# Optic.net
KiCad netlist of a schematic drawn in Altium Designer
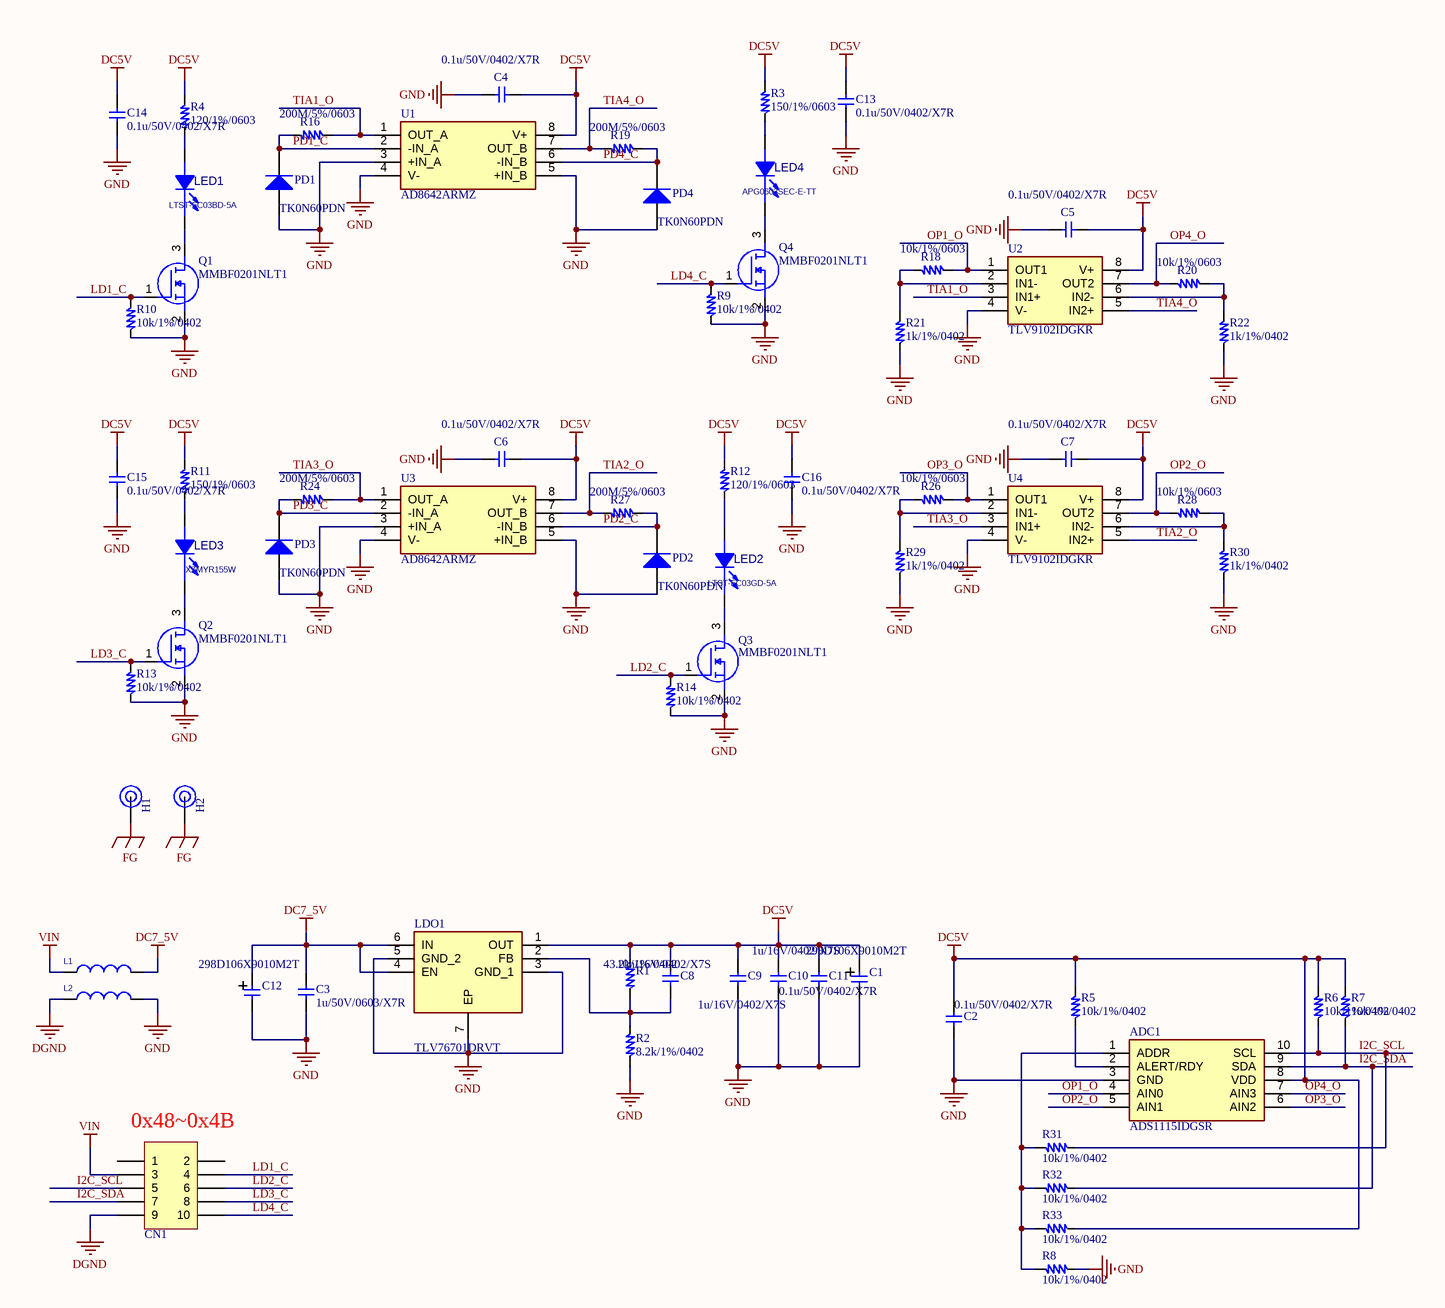
[diagram p0: Optic.SchDoc]

(export (version "E")
  (design (tool "Eeschema 10.0.6"))
  (components
    (comp (ref "ADC1")
      (value "ADS1115IDGSR")
      (footprint "SOP50P490X110-10N")
      (description "類比數位轉換器 - ADC 16B ADC w/ Int MUX PGA Comp Osc & Ref")
      (fields (field (name "MOUSER PART NUMBER") "595-ADS1115IDGSR"))
      (libsource (lib "Biotaitan") (part "ADS1115IDGSR"))
    )
    (comp (ref "C1")
      (value "298D106X9010M2T")
      (footprint "CC0603")
      (description "鉭電容 - 固態 SMD 10uF 10volts 10% M case MAP")
      (libsource (lib "Biotaitan") (part "298D106X9010M2T"))
    )
    (comp (ref "C2")
      (value "0.1u/50V/0402/X7R")
      (footprint "CC0402")
      (description "CAP_MLCC")
      (libsource (lib "Biotaitan") (part "CAP_MLCC"))
    )
    (comp (ref "C3")
      (value "1u/50V/0603/X7R")
      (footprint "CC0603")
      (description "CAP_MLCC")
      (libsource (lib "Biotaitan") (part "CAP_MLCC"))
    )
    (comp (ref "C4")
      (value "0.1u/50V/0402/X7R")
      (footprint "CC0402")
      (description "CAP_MLCC")
      (libsource (lib "Biotaitan") (part "CAP_MLCC"))
    )
    (comp (ref "C5")
      (value "0.1u/50V/0402/X7R")
      (footprint "CC0402")
      (description "CAP_MLCC")
      (libsource (lib "Biotaitan") (part "CAP_MLCC"))
    )
    (comp (ref "C6")
      (value "0.1u/50V/0402/X7R")
      (footprint "CC0402")
      (description "CAP_MLCC")
      (libsource (lib "Biotaitan") (part "CAP_MLCC"))
    )
    (comp (ref "C7")
      (value "0.1u/50V/0402/X7R")
      (footprint "CC0402")
      (description "CAP_MLCC")
      (libsource (lib "Biotaitan") (part "CAP_MLCC"))
    )
    (comp (ref "C8")
      (value "10n/16V/0402/X7S")
      (footprint "CC0402")
      (description "CAP_MLCC")
      (libsource (lib "Biotaitan") (part "CAP_MLCC"))
    )
    (comp (ref "C9")
      (value "1u/16V/0402/X7S")
      (footprint "CC0402")
      (description "CAP_MLCC")
      (libsource (lib "Biotaitan") (part "CAP_MLCC"))
    )
    (comp (ref "C10")
      (value "1u/16V/0402/X7S")
      (footprint "CC0402")
      (description "CAP_MLCC")
      (libsource (lib "Biotaitan") (part "CAP_MLCC"))
    )
    (comp (ref "C11")
      (value "0.1u/50V/0402/X7R")
      (footprint "CC0402")
      (description "CAP_MLCC")
      (libsource (lib "Biotaitan") (part "CAP_MLCC"))
    )
    (comp (ref "C12")
      (value "298D106X9010M2T")
      (footprint "CC0603")
      (description "鉭電容 - 固態 SMD 10uF 10volts 10% M case MAP")
      (libsource (lib "Biotaitan") (part "298D106X9010M2T"))
    )
    (comp (ref "C13")
      (value "0.1u/50V/0402/X7R")
      (footprint "CC0402")
      (description "CAP_MLCC")
      (libsource (lib "Biotaitan") (part "CAP_MLCC"))
    )
    (comp (ref "C14")
      (value "0.1u/50V/0402/X7R")
      (footprint "CC0402")
      (description "CAP_MLCC")
      (libsource (lib "Biotaitan") (part "CAP_MLCC"))
    )
    (comp (ref "C15")
      (value "0.1u/50V/0402/X7R")
      (footprint "CC0402")
      (description "CAP_MLCC")
      (libsource (lib "Biotaitan") (part "CAP_MLCC"))
    )
    (comp (ref "C16")
      (value "0.1u/50V/0402/X7R")
      (footprint "CC0402")
      (description "CAP_MLCC")
      (libsource (lib "Biotaitan") (part "CAP_MLCC"))
    )
    (comp (ref "CN1")
      (value "320-10")
      (footprint "SHDR10W70P254_2X5_2000X850X900P")
      (description "IDC_(100y) VER TH 10POS 2.54MM")
      (libsource (lib "Biotaitan") (part "320-10"))
    )
    (comp (ref "H1")
      (value "Screw_holes_3p5mm")
      (footprint "Screw_holes_2p3mm")
      (description "Screw holes")
      (libsource (lib "Biotaitan") (part "Screw_holes"))
    )
    (comp (ref "H2")
      (value "Screw_holes_3p5mm")
      (footprint "Screw_holes_2p3mm")
      (description "Screw holes")
      (libsource (lib "Biotaitan") (part "Screw_holes"))
    )
    (comp (ref "L1")
      (value "BLM21PG221SN1D")
      (footprint "CC0805")
      (description "Ferrite Bead_220 ohm @ 100 MHz, 2 A, 0805")
      (libsource (lib "Biotaitan") (part "BLM21PG221SN1D"))
    )
    (comp (ref "L2")
      (value "BLM21PG221SN1D")
      (footprint "CC0805")
      (description "Ferrite Bead_220 ohm @ 100 MHz, 2 A, 0805")
      (libsource (lib "Biotaitan") (part "BLM21PG221SN1D"))
    )
    (comp (ref "LDO1")
      (value "TLV76701DRVT")
      (footprint "SON65P200X200X80-7N")
      (libsource (lib "Biotaitan") (part "TLV76701DRVT"))
    )
    (comp (ref "LED1")
      (value "LTST-FC03BD-5A")
      (footprint "LTST_FC03_LED")
      (description "0.65 mm x 0.35 mm SMD LED, 0.2 mm thickness")
      (libsource (lib "Biotaitan") (part "LTST-FC03BD-5A"))
    )
    (comp (ref "LED2")
      (value "LTST-FC03GD-5A")
      (footprint "LTST_FC03_LED")
      (description "0.65 mm x 0.35 mm SMD LED, 0.2 mm thickness")
      (libsource (lib "Biotaitan") (part "LTST-FC03GD-5A"))
    )
    (comp (ref "LED3")
      (value "XZMYR155W")
      (footprint "APG0603_LED")
      (description "0.65 mm x 0.35 mm SMD LED, 0.2 mm thickness")
      (libsource (lib "Biotaitan") (part "XZMYR155W"))
    )
    (comp (ref "LED4")
      (value "APG0603SEC-E-TT")
      (footprint "APG0603_LED")
      (description "0.65 mm x 0.35 mm SMD LED, 0.2 mm thickness")
      (libsource (lib "Biotaitan") (part "APG0603SEC-E-TT"))
    )
    (comp (ref "PD1")
      (value "TK0N60PDN")
      (footprint "TK0N60PDN")
      (description "Si Photo-diode Chip")
      (libsource (lib "Biotaitan") (part "TK0N60PDN"))
    )
    (comp (ref "PD2")
      (value "TK0N60PDN")
      (footprint "TK0N60PDN")
      (description "Si Photo-diode Chip")
      (libsource (lib "Biotaitan") (part "TK0N60PDN"))
    )
    (comp (ref "PD3")
      (value "TK0N60PDN")
      (footprint "TK0N60PDN")
      (description "Si Photo-diode Chip")
      (libsource (lib "Biotaitan") (part "TK0N60PDN"))
    )
    (comp (ref "PD4")
      (value "TK0N60PDN")
      (footprint "TK0N60PDN")
      (description "Si Photo-diode Chip")
      (libsource (lib "Biotaitan") (part "TK0N60PDN"))
    )
    (comp (ref "Q1")
      (value "MMBF0201NLT1")
      (footprint "SOT65P210X110-3N")
      (description "MOSFET (N-Channel)(百年)")
      (libsource (lib "Biotaitan") (part "MMBF0201NLT1"))
    )
    (comp (ref "Q2")
      (value "MMBF0201NLT1")
      (footprint "SOT65P210X110-3N")
      (description "MOSFET (N-Channel)(百年)")
      (libsource (lib "Biotaitan") (part "MMBF0201NLT1"))
    )
    (comp (ref "Q3")
      (value "MMBF0201NLT1")
      (footprint "SOT65P210X110-3N")
      (description "MOSFET (N-Channel)(百年)")
      (libsource (lib "Biotaitan") (part "MMBF0201NLT1"))
    )
    (comp (ref "Q4")
      (value "MMBF0201NLT1")
      (footprint "SOT65P210X110-3N")
      (description "MOSFET (N-Channel)(百年)")
      (libsource (lib "Biotaitan") (part "MMBF0201NLT1"))
    )
    (comp (ref "R1")
      (value "43.2k/1%/0402")
      (footprint "CC0402_R")
      (description "RES_")
      (libsource (lib "Biotaitan") (part "RES_SMD"))
    )
    (comp (ref "R2")
      (value "8.2k/1%/0402")
      (footprint "CC0402_R")
      (description "RES_")
      (libsource (lib "Biotaitan") (part "RES_SMD"))
    )
    (comp (ref "R3")
      (value "150/1%/0603")
      (footprint "CC0603_R")
      (description "RES_")
      (libsource (lib "Biotaitan") (part "RES_SMD"))
    )
    (comp (ref "R4")
      (value "120/1%/0603")
      (footprint "CC0603_R")
      (description "RES_")
      (libsource (lib "Biotaitan") (part "RES_SMD"))
    )
    (comp (ref "R5")
      (value "10k/1%/0402")
      (footprint "CC0402_R")
      (description "RES_")
      (libsource (lib "Biotaitan") (part "RES_SMD"))
    )
    (comp (ref "R6")
      (value "10k/1%/0402")
      (footprint "CC0402_R")
      (description "RES_")
      (libsource (lib "Biotaitan") (part "RES_SMD"))
    )
    (comp (ref "R7")
      (value "10k/1%/0402")
      (footprint "CC0402_R")
      (description "RES_")
      (libsource (lib "Biotaitan") (part "RES_SMD"))
    )
    (comp (ref "R8")
      (value "10k/1%/0402")
      (footprint "CC0402_R")
      (description "RES_")
      (libsource (lib "Biotaitan") (part "RES_SMD"))
    )
    (comp (ref "R9")
      (value "10k/1%/0402")
      (footprint "CC0402_R")
      (description "RES_")
      (libsource (lib "Biotaitan") (part "RES_SMD"))
    )
    (comp (ref "R10")
      (value "10k/1%/0402")
      (footprint "CC0402_R")
      (description "RES_")
      (libsource (lib "Biotaitan") (part "RES_SMD"))
    )
    (comp (ref "R11")
      (value "150/1%/0603")
      (footprint "CC0603_R")
      (description "RES_")
      (libsource (lib "Biotaitan") (part "RES_SMD"))
    )
    (comp (ref "R12")
      (value "120/1%/0603")
      (footprint "CC0603_R")
      (description "RES_")
      (libsource (lib "Biotaitan") (part "RES_SMD"))
    )
    (comp (ref "R13")
      (value "10k/1%/0402")
      (footprint "CC0402_R")
      (description "RES_")
      (libsource (lib "Biotaitan") (part "RES_SMD"))
    )
    (comp (ref "R14")
      (value "10k/1%/0402")
      (footprint "CC0402_R")
      (description "RES_")
      (libsource (lib "Biotaitan") (part "RES_SMD"))
    )
    (comp (ref "R16")
      (value "200M/5%/0603")
      (footprint "CC0603_R")
      (description "RES_")
      (libsource (lib "Biotaitan") (part "RES_SMD"))
    )
    (comp (ref "R18")
      (value "10k/1%/0603")
      (footprint "CC0603_R")
      (description "RES_")
      (libsource (lib "Biotaitan") (part "RES_SMD"))
    )
    (comp (ref "R19")
      (value "200M/5%/0603")
      (footprint "CC0603_R")
      (description "RES_")
      (libsource (lib "Biotaitan") (part "RES_SMD"))
    )
    (comp (ref "R20")
      (value "10k/1%/0603")
      (footprint "CC0603_R")
      (description "RES_")
      (libsource (lib "Biotaitan") (part "RES_SMD"))
    )
    (comp (ref "R21")
      (value "1k/1%/0402")
      (footprint "CC0402_R")
      (description "RES_")
      (libsource (lib "Biotaitan") (part "RES_SMD"))
    )
    (comp (ref "R22")
      (value "1k/1%/0402")
      (footprint "CC0402_R")
      (description "RES_")
      (libsource (lib "Biotaitan") (part "RES_SMD"))
    )
    (comp (ref "R24")
      (value "200M/5%/0603")
      (footprint "CC0603_R")
      (description "RES_")
      (libsource (lib "Biotaitan") (part "RES_SMD"))
    )
    (comp (ref "R26")
      (value "10k/1%/0603")
      (footprint "CC0603_R")
      (description "RES_")
      (libsource (lib "Biotaitan") (part "RES_SMD"))
    )
    (comp (ref "R27")
      (value "200M/5%/0603")
      (footprint "CC0603_R")
      (description "RES_")
      (libsource (lib "Biotaitan") (part "RES_SMD"))
    )
    (comp (ref "R28")
      (value "10k/1%/0603")
      (footprint "CC0603_R")
      (description "RES_")
      (libsource (lib "Biotaitan") (part "RES_SMD"))
    )
    (comp (ref "R29")
      (value "1k/1%/0402")
      (footprint "CC0402_R")
      (description "RES_")
      (libsource (lib "Biotaitan") (part "RES_SMD"))
    )
    (comp (ref "R30")
      (value "1k/1%/0402")
      (footprint "CC0402_R")
      (description "RES_")
      (libsource (lib "Biotaitan") (part "RES_SMD"))
    )
    (comp (ref "R31")
      (value "10k/1%/0402")
      (footprint "CC0402_R")
      (description "RES_")
      (libsource (lib "Biotaitan") (part "RES_SMD"))
    )
    (comp (ref "R32")
      (value "10k/1%/0402")
      (footprint "CC0402_R")
      (description "RES_")
      (libsource (lib "Biotaitan") (part "RES_SMD"))
    )
    (comp (ref "R33")
      (value "10k/1%/0402")
      (footprint "CC0402_R")
      (description "RES_")
      (libsource (lib "Biotaitan") (part "RES_SMD"))
    )
    (comp (ref "U1")
      (value "AD8642ARMZ")
      (footprint "SOP65P490X110-8N")
      (description "精密放大器 DUAL LOW POWER/IBIAS, R-R JFET AMP")
      (fields (field (name "MOUSER PART NUMBER") "584-AD8642ARMZ"))
      (libsource (lib "Biotaitan") (part "AD8642ARMZ"))
    )
    (comp (ref "U2")
      (value "TLV9102IDGKR")
      (footprint "SOP65P490X110-8N")
      (description "運算放大器 - 運放器")
      (fields (field (name "MOUSER PART NUMBER") "595-TLV9102IDGKR"))
      (libsource (lib "Biotaitan") (part "TLV9102IDGKR"))
    )
    (comp (ref "U3")
      (value "AD8642ARMZ")
      (footprint "SOP65P490X110-8N")
      (description "精密放大器 DUAL LOW POWER/IBIAS, R-R JFET AMP")
      (fields (field (name "MOUSER PART NUMBER") "584-AD8642ARMZ"))
      (libsource (lib "Biotaitan") (part "AD8642ARMZ"))
    )
    (comp (ref "U4")
      (value "TLV9102IDGKR")
      (footprint "SOP65P490X110-8N")
      (description "運算放大器 - 運放器")
      (fields (field (name "MOUSER PART NUMBER") "595-TLV9102IDGKR"))
      (libsource (lib "Biotaitan") (part "TLV9102IDGKR"))
    )
  )
  (nets
    (net (code "1") (name "/I2C_SCL") (class "Default")
      (node (ref "ADC1") (pin "10") (pinfunction "SCL_10") (pintype "passive"))
      (node (ref "CN1") (pin "5") (pinfunction "5_5") (pintype "passive"))
      (node (ref "R31") (pin "1") (pinfunction "1_1") (pintype "passive"))
      (node (ref "R6") (pin "1") (pinfunction "1_1") (pintype "passive"))
    )
    (net (code "2") (name "/I2C_SDA") (class "Default")
      (node (ref "ADC1") (pin "9") (pinfunction "SDA_9") (pintype "passive"))
      (node (ref "CN1") (pin "7") (pinfunction "7_7") (pintype "passive"))
      (node (ref "R32") (pin "1") (pinfunction "1_1") (pintype "passive"))
      (node (ref "R7") (pin "1") (pinfunction "1_1") (pintype "passive"))
    )
    (net (code "3") (name "/LD1_C") (class "Default")
      (node (ref "CN1") (pin "4") (pinfunction "4_4") (pintype "passive"))
      (node (ref "Q1") (pin "1") (pinfunction "G_1") (pintype "passive"))
      (node (ref "R10") (pin "2") (pinfunction "2_2") (pintype "passive"))
    )
    (net (code "4") (name "/LD2_C") (class "Default")
      (node (ref "CN1") (pin "6") (pinfunction "6_6") (pintype "passive"))
      (node (ref "Q3") (pin "1") (pinfunction "G_1") (pintype "passive"))
      (node (ref "R14") (pin "2") (pinfunction "2_2") (pintype "passive"))
    )
    (net (code "5") (name "/LD3_C") (class "Default")
      (node (ref "CN1") (pin "8") (pinfunction "8_8") (pintype "passive"))
      (node (ref "Q2") (pin "1") (pinfunction "G_1") (pintype "passive"))
      (node (ref "R13") (pin "2") (pinfunction "2_2") (pintype "passive"))
    )
    (net (code "6") (name "/LD4_C") (class "Default")
      (node (ref "CN1") (pin "10") (pinfunction "10_10") (pintype "passive"))
      (node (ref "Q4") (pin "1") (pinfunction "G_1") (pintype "passive"))
      (node (ref "R9") (pin "2") (pinfunction "2_2") (pintype "passive"))
    )
    (net (code "7") (name "/OP1_O") (class "Default")
      (node (ref "ADC1") (pin "4") (pinfunction "AIN0_4") (pintype "passive"))
      (node (ref "R18") (pin "2") (pinfunction "2_2") (pintype "passive"))
      (node (ref "U2") (pin "1") (pinfunction "OUT1_1") (pintype "passive"))
    )
    (net (code "8") (name "/OP2_O") (class "Default")
      (node (ref "ADC1") (pin "5") (pinfunction "AIN1_5") (pintype "passive"))
      (node (ref "R28") (pin "1") (pinfunction "1_1") (pintype "passive"))
      (node (ref "U4") (pin "7") (pinfunction "OUT2_7") (pintype "passive"))
    )
    (net (code "9") (name "/OP3_O") (class "Default")
      (node (ref "ADC1") (pin "6") (pinfunction "AIN2_6") (pintype "passive"))
      (node (ref "R26") (pin "2") (pinfunction "2_2") (pintype "passive"))
      (node (ref "U4") (pin "1") (pinfunction "OUT1_1") (pintype "passive"))
    )
    (net (code "10") (name "/OP4_O") (class "Default")
      (node (ref "ADC1") (pin "7") (pinfunction "AIN3_7") (pintype "passive"))
      (node (ref "R20") (pin "1") (pinfunction "1_1") (pintype "passive"))
      (node (ref "U2") (pin "7") (pinfunction "OUT2_7") (pintype "passive"))
    )
    (net (code "11") (name "/PD1_C") (class "Default")
      (node (ref "PD1") (pin "1") (pinfunction "K_1") (pintype "passive"))
      (node (ref "R16") (pin "1") (pinfunction "1_1") (pintype "passive"))
      (node (ref "U1") (pin "2") (pinfunction "-IN_A_2") (pintype "passive"))
    )
    (net (code "12") (name "/PD2_C") (class "Default")
      (node (ref "PD2") (pin "1") (pinfunction "K_1") (pintype "passive"))
      (node (ref "R27") (pin "2") (pinfunction "2_2") (pintype "passive"))
      (node (ref "U3") (pin "6") (pinfunction "-IN_B_6") (pintype "passive"))
    )
    (net (code "13") (name "/PD3_C") (class "Default")
      (node (ref "PD3") (pin "1") (pinfunction "K_1") (pintype "passive"))
      (node (ref "R24") (pin "1") (pinfunction "1_1") (pintype "passive"))
      (node (ref "U3") (pin "2") (pinfunction "-IN_A_2") (pintype "passive"))
    )
    (net (code "14") (name "/PD4_C") (class "Default")
      (node (ref "PD4") (pin "1") (pinfunction "K_1") (pintype "passive"))
      (node (ref "R19") (pin "2") (pinfunction "2_2") (pintype "passive"))
      (node (ref "U1") (pin "6") (pinfunction "-IN_B_6") (pintype "passive"))
    )
    (net (code "15") (name "/TIA1_O") (class "Default")
      (node (ref "R16") (pin "2") (pinfunction "2_2") (pintype "passive"))
      (node (ref "U1") (pin "1") (pinfunction "OUT_A_1") (pintype "passive"))
      (node (ref "U2") (pin "3") (pinfunction "IN1+_3") (pintype "passive"))
    )
    (net (code "16") (name "/TIA2_O") (class "Default")
      (node (ref "R27") (pin "1") (pinfunction "1_1") (pintype "passive"))
      (node (ref "U3") (pin "7") (pinfunction "OUT_B_7") (pintype "passive"))
      (node (ref "U4") (pin "5") (pinfunction "IN2+_5") (pintype "passive"))
    )
    (net (code "17") (name "/TIA3_O") (class "Default")
      (node (ref "R24") (pin "2") (pinfunction "2_2") (pintype "passive"))
      (node (ref "U3") (pin "1") (pinfunction "OUT_A_1") (pintype "passive"))
      (node (ref "U4") (pin "3") (pinfunction "IN1+_3") (pintype "passive"))
    )
    (net (code "18") (name "/TIA4_O") (class "Default")
      (node (ref "R19") (pin "1") (pinfunction "1_1") (pintype "passive"))
      (node (ref "U1") (pin "7") (pinfunction "OUT_B_7") (pintype "passive"))
      (node (ref "U2") (pin "5") (pinfunction "IN2+_5") (pintype "passive"))
    )
    (net (code "19") (name "DC5V") (class "Default")
      (node (ref "ADC1") (pin "8") (pinfunction "VDD_8") (pintype "passive"))
      (node (ref "C1") (pin "2") (pinfunction "2_2") (pintype "passive"))
      (node (ref "C10") (pin "1") (pinfunction "1_1") (pintype "passive"))
      (node (ref "C11") (pin "1") (pinfunction "1_1") (pintype "passive"))
      (node (ref "C13") (pin "2") (pinfunction "2_2") (pintype "passive"))
      (node (ref "C14") (pin "2") (pinfunction "2_2") (pintype "passive"))
      (node (ref "C15") (pin "2") (pinfunction "2_2") (pintype "passive"))
      (node (ref "C16") (pin "2") (pinfunction "2_2") (pintype "passive"))
      (node (ref "C2") (pin "1") (pinfunction "1_1") (pintype "passive"))
      (node (ref "C4") (pin "2") (pinfunction "2_2") (pintype "passive"))
      (node (ref "C5") (pin "2") (pinfunction "2_2") (pintype "passive"))
      (node (ref "C6") (pin "2") (pinfunction "2_2") (pintype "passive"))
      (node (ref "C7") (pin "2") (pinfunction "2_2") (pintype "passive"))
      (node (ref "C8") (pin "1") (pinfunction "1_1") (pintype "passive"))
      (node (ref "C9") (pin "1") (pinfunction "1_1") (pintype "passive"))
      (node (ref "LDO1") (pin "1") (pinfunction "OUT_1") (pintype "passive"))
      (node (ref "R1") (pin "1") (pinfunction "1_1") (pintype "passive"))
      (node (ref "R11") (pin "2") (pinfunction "2_2") (pintype "passive"))
      (node (ref "R12") (pin "2") (pinfunction "2_2") (pintype "passive"))
      (node (ref "R3") (pin "2") (pinfunction "2_2") (pintype "passive"))
      (node (ref "R33") (pin "1") (pinfunction "1_1") (pintype "passive"))
      (node (ref "R4") (pin "2") (pinfunction "2_2") (pintype "passive"))
      (node (ref "R5") (pin "2") (pinfunction "2_2") (pintype "passive"))
      (node (ref "R6") (pin "2") (pinfunction "2_2") (pintype "passive"))
      (node (ref "R7") (pin "2") (pinfunction "2_2") (pintype "passive"))
      (node (ref "U1") (pin "8") (pinfunction "V+_8") (pintype "passive"))
      (node (ref "U2") (pin "8") (pinfunction "V+_8") (pintype "passive"))
      (node (ref "U3") (pin "8") (pinfunction "V+_8") (pintype "passive"))
      (node (ref "U4") (pin "8") (pinfunction "V+_8") (pintype "passive"))
    )
    (net (code "20") (name "DC7_5V") (class "Default")
      (node (ref "C12") (pin "2") (pinfunction "2_2") (pintype "passive"))
      (node (ref "C3") (pin "1") (pinfunction "1_1") (pintype "passive"))
      (node (ref "L1") (pin "2") (pinfunction "2_2") (pintype "passive"))
      (node (ref "LDO1") (pin "4") (pinfunction "EN_4") (pintype "passive"))
      (node (ref "LDO1") (pin "6") (pinfunction "IN_6") (pintype "passive"))
    )
    (net (code "21") (name "DGND") (class "Default")
      (node (ref "CN1") (pin "9") (pinfunction "9_9") (pintype "passive"))
      (node (ref "L2") (pin "1") (pinfunction "1_1") (pintype "passive"))
    )
    (net (code "22") (name "FG") (class "Default")
      (node (ref "H1") (pin "1") (pinfunction "1_1") (pintype "passive"))
      (node (ref "H2") (pin "1") (pinfunction "1_1") (pintype "passive"))
    )
    (net (code "23") (name "GND") (class "Default")
      (node (ref "ADC1") (pin "3") (pinfunction "GND_3") (pintype "passive"))
      (node (ref "C1") (pin "1") (pinfunction "1_1") (pintype "passive"))
      (node (ref "C10") (pin "2") (pinfunction "2_2") (pintype "passive"))
      (node (ref "C11") (pin "2") (pinfunction "2_2") (pintype "passive"))
      (node (ref "C12") (pin "1") (pinfunction "1_1") (pintype "passive"))
      (node (ref "C13") (pin "1") (pinfunction "1_1") (pintype "passive"))
      (node (ref "C14") (pin "1") (pinfunction "1_1") (pintype "passive"))
      (node (ref "C15") (pin "1") (pinfunction "1_1") (pintype "passive"))
      (node (ref "C16") (pin "1") (pinfunction "1_1") (pintype "passive"))
      (node (ref "C2") (pin "2") (pinfunction "2_2") (pintype "passive"))
      (node (ref "C3") (pin "2") (pinfunction "2_2") (pintype "passive"))
      (node (ref "C4") (pin "1") (pinfunction "1_1") (pintype "passive"))
      (node (ref "C5") (pin "1") (pinfunction "1_1") (pintype "passive"))
      (node (ref "C6") (pin "1") (pinfunction "1_1") (pintype "passive"))
      (node (ref "C7") (pin "1") (pinfunction "1_1") (pintype "passive"))
      (node (ref "C9") (pin "2") (pinfunction "2_2") (pintype "passive"))
      (node (ref "L2") (pin "2") (pinfunction "2_2") (pintype "passive"))
      (node (ref "LDO1") (pin "3") (pinfunction "GND_1_3") (pintype "passive"))
      (node (ref "LDO1") (pin "5") (pinfunction "GND_2_5") (pintype "passive"))
      (node (ref "LDO1") (pin "7") (pinfunction "EP_7") (pintype "passive"))
      (node (ref "PD1") (pin "2") (pinfunction "A_2") (pintype "passive"))
      (node (ref "PD2") (pin "2") (pinfunction "A_2") (pintype "passive"))
      (node (ref "PD3") (pin "2") (pinfunction "A_2") (pintype "passive"))
      (node (ref "PD4") (pin "2") (pinfunction "A_2") (pintype "passive"))
      (node (ref "Q1") (pin "2") (pinfunction "S_2") (pintype "passive"))
      (node (ref "Q2") (pin "2") (pinfunction "S_2") (pintype "passive"))
      (node (ref "Q3") (pin "2") (pinfunction "S_2") (pintype "passive"))
      (node (ref "Q4") (pin "2") (pinfunction "S_2") (pintype "passive"))
      (node (ref "R10") (pin "1") (pinfunction "1_1") (pintype "passive"))
      (node (ref "R13") (pin "1") (pinfunction "1_1") (pintype "passive"))
      (node (ref "R14") (pin "1") (pinfunction "1_1") (pintype "passive"))
      (node (ref "R2") (pin "2") (pinfunction "2_2") (pintype "passive"))
      (node (ref "R21") (pin "1") (pinfunction "1_1") (pintype "passive"))
      (node (ref "R22") (pin "1") (pinfunction "1_1") (pintype "passive"))
      (node (ref "R29") (pin "1") (pinfunction "1_1") (pintype "passive"))
      (node (ref "R30") (pin "1") (pinfunction "1_1") (pintype "passive"))
      (node (ref "R8") (pin "1") (pinfunction "1_1") (pintype "passive"))
      (node (ref "R9") (pin "1") (pinfunction "1_1") (pintype "passive"))
      (node (ref "U1") (pin "3") (pinfunction "+IN_A_3") (pintype "passive"))
      (node (ref "U1") (pin "4") (pinfunction "V-_4") (pintype "passive"))
      (node (ref "U1") (pin "5") (pinfunction "+IN_B_5") (pintype "passive"))
      (node (ref "U2") (pin "4") (pinfunction "V-_4") (pintype "passive"))
      (node (ref "U3") (pin "3") (pinfunction "+IN_A_3") (pintype "passive"))
      (node (ref "U3") (pin "4") (pinfunction "V-_4") (pintype "passive"))
      (node (ref "U3") (pin "5") (pinfunction "+IN_B_5") (pintype "passive"))
      (node (ref "U4") (pin "4") (pinfunction "V-_4") (pintype "passive"))
    )
    (net (code "24") (name "Net-(ADC1-ADDR)") (class "Default")
      (node (ref "ADC1") (pin "1") (pinfunction "ADDR_1") (pintype "passive"))
      (node (ref "R31") (pin "2") (pinfunction "2_2") (pintype "passive"))
      (node (ref "R32") (pin "2") (pinfunction "2_2") (pintype "passive"))
      (node (ref "R33") (pin "2") (pinfunction "2_2") (pintype "passive"))
      (node (ref "R8") (pin "2") (pinfunction "2_2") (pintype "passive"))
    )
    (net (code "25") (name "Net-(ADC1-ALERT{slash}RDY)") (class "Default")
      (node (ref "ADC1") (pin "2") (pinfunction "ALERT/RDY_2") (pintype "passive"))
      (node (ref "R5") (pin "1") (pinfunction "1_1") (pintype "passive"))
    )
    (net (code "26") (name "Net-(LDO1-FB)") (class "Default")
      (node (ref "C8") (pin "2") (pinfunction "2_2") (pintype "passive"))
      (node (ref "LDO1") (pin "2") (pinfunction "FB_2") (pintype "passive"))
      (node (ref "R1") (pin "2") (pinfunction "2_2") (pintype "passive"))
      (node (ref "R2") (pin "1") (pinfunction "1_1") (pintype "passive"))
    )
    (net (code "27") (name "Net-(LED1-ANODE)") (class "Default")
      (node (ref "LED1") (pin "2") (pinfunction "ANODE_2") (pintype "passive"))
      (node (ref "R4") (pin "1") (pinfunction "1_1") (pintype "passive"))
    )
    (net (code "28") (name "Net-(LED1-CATHODE)") (class "Default")
      (node (ref "LED1") (pin "1") (pinfunction "CATHODE_1") (pintype "passive"))
      (node (ref "Q1") (pin "3") (pinfunction "D_3") (pintype "passive"))
    )
    (net (code "29") (name "Net-(LED2-ANODE)") (class "Default")
      (node (ref "LED2") (pin "2") (pinfunction "ANODE_2") (pintype "passive"))
      (node (ref "R12") (pin "1") (pinfunction "1_1") (pintype "passive"))
    )
    (net (code "30") (name "Net-(LED2-CATHODE)") (class "Default")
      (node (ref "LED2") (pin "1") (pinfunction "CATHODE_1") (pintype "passive"))
      (node (ref "Q3") (pin "3") (pinfunction "D_3") (pintype "passive"))
    )
    (net (code "31") (name "Net-(LED3-ANODE)") (class "Default")
      (node (ref "LED3") (pin "2") (pinfunction "ANODE_2") (pintype "passive"))
      (node (ref "R11") (pin "1") (pinfunction "1_1") (pintype "passive"))
    )
    (net (code "32") (name "Net-(LED3-CATHODE)") (class "Default")
      (node (ref "LED3") (pin "1") (pinfunction "CATHODE_1") (pintype "passive"))
      (node (ref "Q2") (pin "3") (pinfunction "D_3") (pintype "passive"))
    )
    (net (code "33") (name "Net-(LED4-ANODE)") (class "Default")
      (node (ref "LED4") (pin "2") (pinfunction "ANODE_2") (pintype "passive"))
      (node (ref "R3") (pin "1") (pinfunction "1_1") (pintype "passive"))
    )
    (net (code "34") (name "Net-(LED4-CATHODE)") (class "Default")
      (node (ref "LED4") (pin "1") (pinfunction "CATHODE_1") (pintype "passive"))
      (node (ref "Q4") (pin "3") (pinfunction "D_3") (pintype "passive"))
    )
    (net (code "35") (name "Net-(U2-IN1-)") (class "Default")
      (node (ref "R18") (pin "1") (pinfunction "1_1") (pintype "passive"))
      (node (ref "R21") (pin "2") (pinfunction "2_2") (pintype "passive"))
      (node (ref "U2") (pin "2") (pinfunction "IN1-_2") (pintype "passive"))
    )
    (net (code "36") (name "Net-(U2-IN2-)") (class "Default")
      (node (ref "R20") (pin "2") (pinfunction "2_2") (pintype "passive"))
      (node (ref "R22") (pin "2") (pinfunction "2_2") (pintype "passive"))
      (node (ref "U2") (pin "6") (pinfunction "IN2-_6") (pintype "passive"))
    )
    (net (code "37") (name "Net-(U4-IN1-)") (class "Default")
      (node (ref "R26") (pin "1") (pinfunction "1_1") (pintype "passive"))
      (node (ref "R29") (pin "2") (pinfunction "2_2") (pintype "passive"))
      (node (ref "U4") (pin "2") (pinfunction "IN1-_2") (pintype "passive"))
    )
    (net (code "38") (name "Net-(U4-IN2-)") (class "Default")
      (node (ref "R28") (pin "2") (pinfunction "2_2") (pintype "passive"))
      (node (ref "R30") (pin "2") (pinfunction "2_2") (pintype "passive"))
      (node (ref "U4") (pin "6") (pinfunction "IN2-_6") (pintype "passive"))
    )
    (net (code "39") (name "VIN") (class "Default")
      (node (ref "CN1") (pin "3") (pinfunction "3_3") (pintype "passive"))
      (node (ref "L1") (pin "1") (pinfunction "1_1") (pintype "passive"))
    )
    (net (code "40") (name "unconnected-(CN1-Pad1)") (class "Default")
      (node (ref "CN1") (pin "1") (pinfunction "1_1") (pintype "passive"))
    )
    (net (code "41") (name "unconnected-(CN1-Pad2)") (class "Default")
      (node (ref "CN1") (pin "2") (pinfunction "2_2") (pintype "passive"))
    )
  )
)
